# schemat.net
KiCad netlist of a schematic drawn in EAGLE
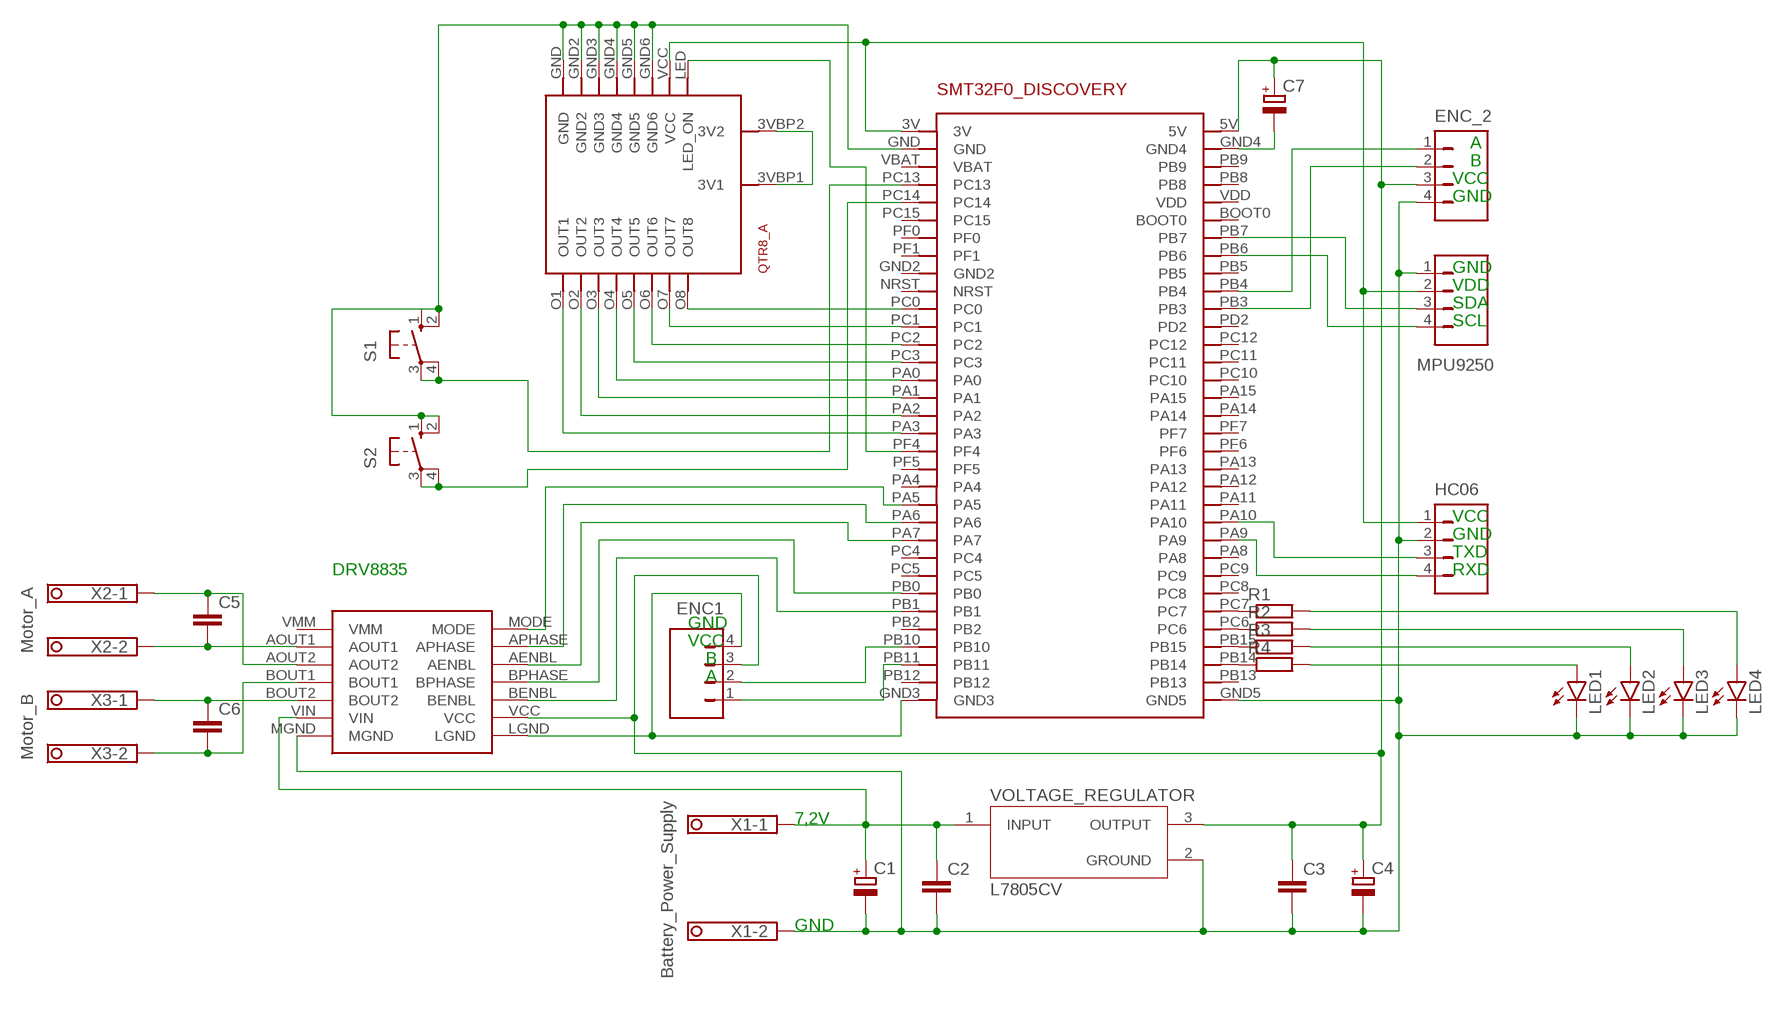
[diagram p0: schematic, sheet 1]

(export (version "E")
  (design (tool "Eeschema 10.0.6"))
  (components
    (comp (ref "C1")
      (value "CPOL-EUE2.5-6")
      (footprint "eagle-import:E2,5-6")
      (libsource (lib "eagle-import") (part "CPOL-EUE2.5-6"))
    )
    (comp (ref "C2")
      (value "C-EU025-024X044")
      (footprint "eagle-import:C025-024X044")
      (libsource (lib "eagle-import") (part "C-EU025-024X044"))
    )
    (comp (ref "C3")
      (value "C-EU025-024X044")
      (footprint "eagle-import:C025-024X044")
      (libsource (lib "eagle-import") (part "C-EU025-024X044"))
    )
    (comp (ref "C4")
      (value "CPOL-EUE2.5-6")
      (footprint "eagle-import:E2,5-6")
      (libsource (lib "eagle-import") (part "CPOL-EUE2.5-6"))
    )
    (comp (ref "C5")
      (value "C-EU025-024X044")
      (footprint "eagle-import:C025-024X044")
      (libsource (lib "eagle-import") (part "C-EU025-024X044"))
    )
    (comp (ref "C6")
      (value "C-EU025-024X044")
      (footprint "eagle-import:C025-024X044")
      (libsource (lib "eagle-import") (part "C-EU025-024X044"))
    )
    (comp (ref "C7")
      (value "CPOL-EUE2.5-6")
      (footprint "eagle-import:E2,5-6")
      (libsource (lib "eagle-import") (part "CPOL-EUE2.5-6"))
    )
    (comp (ref "DRV8835")
      (value "POLOLU_MOTOR_DRV8835THROUGHHOLE")
      (footprint "eagle-import:POLOLU_MOTOR_DRV_DRV8835")
      (libsource (lib "eagle-import") (part "POLOLU_MOTOR_DRV8835THROUGHHOLE"))
    )
    (comp (ref "ENC1")
      (value "JP4E")
      (footprint "eagle-import:JP4")
      (libsource (lib "eagle-import") (part "JP4E"))
    )
    (comp (ref "ENC_2")
      (value "JP4E")
      (footprint "eagle-import:JP4")
      (libsource (lib "eagle-import") (part "JP4E"))
    )
    (comp (ref "HC06")
      (value "JP4E")
      (footprint "eagle-import:JP4")
      (libsource (lib "eagle-import") (part "JP4E"))
    )
    (comp (ref "LED1")
      (value "LEDB152")
      (footprint "eagle-import:Q62902-B152")
      (libsource (lib "eagle-import") (part "LEDB152"))
    )
    (comp (ref "LED2")
      (value "LEDB152")
      (footprint "eagle-import:Q62902-B152")
      (libsource (lib "eagle-import") (part "LEDB152"))
    )
    (comp (ref "LED3")
      (value "LEDB152")
      (footprint "eagle-import:Q62902-B152")
      (libsource (lib "eagle-import") (part "LEDB152"))
    )
    (comp (ref "LED4")
      (value "LEDB152")
      (footprint "eagle-import:Q62902-B152")
      (libsource (lib "eagle-import") (part "LEDB152"))
    )
    (comp (ref "MPU9250")
      (value "JP4E")
      (footprint "eagle-import:JP4")
      (libsource (lib "eagle-import") (part "JP4E"))
    )
    (comp (ref "R1")
      (value "R-EU_0207/7")
      (footprint "eagle-import:0207_7")
      (libsource (lib "eagle-import") (part "R-EU_0207/7"))
    )
    (comp (ref "R2")
      (value "R-EU_0207/7")
      (footprint "eagle-import:0207_7")
      (libsource (lib "eagle-import") (part "R-EU_0207/7"))
    )
    (comp (ref "R3")
      (value "R-EU_0207/7")
      (footprint "eagle-import:0207_7")
      (libsource (lib "eagle-import") (part "R-EU_0207/7"))
    )
    (comp (ref "R4")
      (value "R-EU_0207/7")
      (footprint "eagle-import:0207_7")
      (libsource (lib "eagle-import") (part "R-EU_0207/7"))
    )
    (comp (ref "S1")
      (value "10-XX")
      (footprint "eagle-import:B3F-10XX")
      (fields (field (name "MPN") "B3F-1000"))
      (libsource (lib "eagle-import") (part "10-XX"))
    )
    (comp (ref "S2")
      (value "10-XX")
      (footprint "eagle-import:B3F-10XX")
      (fields (field (name "MPN") "B3F-1000"))
      (libsource (lib "eagle-import") (part "10-XX"))
    )
    (comp (ref "SMT32F0_DISCOVERY")
      (value "STM32F0_DISCOVERY")
      (footprint "eagle-import:STM32F0_DISCOVERY")
      (libsource (lib "eagle-import") (part "STM32F0_DISCOVERY"))
    )
    (comp (ref "U$1")
      (value "QTR8_A")
      (footprint "eagle-import:QTR8_A")
      (libsource (lib "eagle-import") (part "QTR8_A"))
    )
    (comp (ref "VOLTAGE_REGULATOR")
      (value "L7805CV")
      (footprint "eagle-import:TO255P1040X460X1968-3")
      (fields (field (name "MF") "STMicroelectronics"))
      (libsource (lib "eagle-import") (part "L7805CV"))
    )
    (comp (ref "X1")
      (value "Battery_Power_Supply")
      (footprint "eagle-import:1751248")
      (libsource (lib "eagle-import") (part "1751248"))
    )
    (comp (ref "X2")
      (value "Motor_A")
      (footprint "eagle-import:1751248")
      (libsource (lib "eagle-import") (part "1751248"))
    )
    (comp (ref "X3")
      (value "Motor_B")
      (footprint "eagle-import:1751248")
      (libsource (lib "eagle-import") (part "1751248"))
    )
  )
  (nets
    (net (code "1") (name "Net-(C7-Pad-)") (class "Default")
      (node (ref "C7") (pin "-") (pinfunction "-_-") (pintype "passive"))
      (node (ref "SMT32F0_DISCOVERY") (pin "GND4") (pinfunction "GND4_GND4") (pintype "bidirectional"))
    )
    (net (code "2") (name "Net-(DRV8835-PadAENBL)") (class "Default")
      (node (ref "DRV8835") (pin "AENBL") (pinfunction "AENBL_AENBL") (pintype "bidirectional"))
      (node (ref "SMT32F0_DISCOVERY") (pin "PA7") (pinfunction "PA7_PA7") (pintype "bidirectional"))
    )
    (net (code "3") (name "Net-(DRV8835-PadAPHASE)") (class "Default")
      (node (ref "DRV8835") (pin "APHASE") (pinfunction "APHASE_APHASE") (pintype "bidirectional"))
      (node (ref "SMT32F0_DISCOVERY") (pin "PA6") (pinfunction "PA6_PA6") (pintype "bidirectional"))
    )
    (net (code "4") (name "Net-(DRV8835-PadBENBL)") (class "Default")
      (node (ref "DRV8835") (pin "BENBL") (pinfunction "BENBL_BENBL") (pintype "bidirectional"))
      (node (ref "SMT32F0_DISCOVERY") (pin "PB1") (pinfunction "PB1_PB1") (pintype "bidirectional"))
    )
    (net (code "5") (name "Net-(DRV8835-PadBPHASE)") (class "Default")
      (node (ref "DRV8835") (pin "BPHASE") (pinfunction "BPHASE_BPHASE") (pintype "bidirectional"))
      (node (ref "SMT32F0_DISCOVERY") (pin "PB0") (pinfunction "PB0_PB0") (pintype "bidirectional"))
    )
    (net (code "6") (name "Net-(DRV8835-PadLGND)") (class "Default")
      (node (ref "DRV8835") (pin "LGND") (pinfunction "LGND_LGND") (pintype "bidirectional"))
      (node (ref "ENC1") (pin "4") (pinfunction "4_4") (pintype "passive"))
      (node (ref "SMT32F0_DISCOVERY") (pin "GND3") (pinfunction "GND3_GND3") (pintype "bidirectional"))
    )
    (net (code "7") (name "Net-(DRV8835-PadMODE)") (class "Default")
      (node (ref "DRV8835") (pin "MODE") (pinfunction "MODE_MODE") (pintype "bidirectional"))
      (node (ref "SMT32F0_DISCOVERY") (pin "PA5") (pinfunction "PA5_PA5") (pintype "bidirectional"))
    )
    (net (code "8") (name "Net-(ENC1-Pad1)") (class "Default")
      (node (ref "ENC1") (pin "1") (pinfunction "1_1") (pintype "passive"))
      (node (ref "SMT32F0_DISCOVERY") (pin "PB11") (pinfunction "PB11_PB11") (pintype "bidirectional"))
    )
    (net (code "9") (name "Net-(ENC1-Pad2)") (class "Default")
      (node (ref "ENC1") (pin "2") (pinfunction "2_2") (pintype "passive"))
      (node (ref "SMT32F0_DISCOVERY") (pin "PB10") (pinfunction "PB10_PB10") (pintype "bidirectional"))
    )
    (net (code "10") (name "Net-(ENC_2-Pad1)") (class "Default")
      (node (ref "ENC_2") (pin "1") (pinfunction "1_1") (pintype "passive"))
      (node (ref "SMT32F0_DISCOVERY") (pin "PB4") (pinfunction "PB4_PB4") (pintype "bidirectional"))
    )
    (net (code "11") (name "Net-(ENC_2-Pad2)") (class "Default")
      (node (ref "ENC_2") (pin "2") (pinfunction "2_2") (pintype "passive"))
      (node (ref "SMT32F0_DISCOVERY") (pin "PB3") (pinfunction "PB3_PB3") (pintype "bidirectional"))
    )
    (net (code "12") (name "Net-(HC06-Pad1)") (class "Default")
      (node (ref "HC06") (pin "1") (pinfunction "1_1") (pintype "passive"))
      (node (ref "MPU9250") (pin "2") (pinfunction "2_2") (pintype "passive"))
      (node (ref "SMT32F0_DISCOVERY") (pin "3V") (pinfunction "3V_3V") (pintype "bidirectional"))
      (node (ref "U$1") (pin "VCC") (pinfunction "VCC_VCC") (pintype "bidirectional"))
    )
    (net (code "13") (name "Net-(HC06-Pad3)") (class "Default")
      (node (ref "HC06") (pin "3") (pinfunction "3_3") (pintype "passive"))
      (node (ref "SMT32F0_DISCOVERY") (pin "PA10") (pinfunction "PA10_PA10") (pintype "bidirectional"))
    )
    (net (code "14") (name "Net-(HC06-Pad4)") (class "Default")
      (node (ref "HC06") (pin "4") (pinfunction "4_4") (pintype "passive"))
      (node (ref "SMT32F0_DISCOVERY") (pin "PA9") (pinfunction "PA9_PA9") (pintype "bidirectional"))
    )
    (net (code "15") (name "Net-(LED1-C)") (class "Default")
      (node (ref "C1") (pin "-") (pinfunction "-_-") (pintype "passive"))
      (node (ref "C2") (pin "2") (pinfunction "2_2") (pintype "passive"))
      (node (ref "C3") (pin "2") (pinfunction "2_2") (pintype "passive"))
      (node (ref "C4") (pin "-") (pinfunction "-_-") (pintype "passive"))
      (node (ref "DRV8835") (pin "MGND") (pinfunction "MGND_MGND") (pintype "bidirectional"))
      (node (ref "ENC_2") (pin "4") (pinfunction "4_4") (pintype "passive"))
      (node (ref "HC06") (pin "2") (pinfunction "2_2") (pintype "passive"))
      (node (ref "LED1") (pin "K") (pinfunction "C_K") (pintype "passive"))
      (node (ref "LED2") (pin "K") (pinfunction "C_K") (pintype "passive"))
      (node (ref "LED3") (pin "K") (pinfunction "C_K") (pintype "passive"))
      (node (ref "LED4") (pin "K") (pinfunction "C_K") (pintype "passive"))
      (node (ref "MPU9250") (pin "1") (pinfunction "1_1") (pintype "passive"))
      (node (ref "SMT32F0_DISCOVERY") (pin "GND5") (pinfunction "GND5_GND5") (pintype "bidirectional"))
      (node (ref "VOLTAGE_REGULATOR") (pin "2") (pinfunction "GROUND_2") (pintype "power_in"))
      (node (ref "X1") (pin "2") (pinfunction "K_2") (pintype "passive"))
    )
    (net (code "16") (name "Net-(LED1-PadA)") (class "Default")
      (node (ref "LED1") (pin "A") (pinfunction "A_A") (pintype "passive"))
      (node (ref "R4") (pin "2") (pinfunction "2_2") (pintype "passive"))
    )
    (net (code "17") (name "Net-(LED2-PadA)") (class "Default")
      (node (ref "LED2") (pin "A") (pinfunction "A_A") (pintype "passive"))
      (node (ref "R3") (pin "2") (pinfunction "2_2") (pintype "passive"))
    )
    (net (code "18") (name "Net-(LED3-PadA)") (class "Default")
      (node (ref "LED3") (pin "A") (pinfunction "A_A") (pintype "passive"))
      (node (ref "R2") (pin "2") (pinfunction "2_2") (pintype "passive"))
    )
    (net (code "19") (name "Net-(LED4-PadA)") (class "Default")
      (node (ref "LED4") (pin "A") (pinfunction "A_A") (pintype "passive"))
      (node (ref "R1") (pin "2") (pinfunction "2_2") (pintype "passive"))
    )
    (net (code "20") (name "Net-(MPU9250-Pad3)") (class "Default")
      (node (ref "MPU9250") (pin "3") (pinfunction "3_3") (pintype "passive"))
      (node (ref "SMT32F0_DISCOVERY") (pin "PB7") (pinfunction "PB7_PB7") (pintype "bidirectional"))
    )
    (net (code "21") (name "Net-(MPU9250-Pad4)") (class "Default")
      (node (ref "MPU9250") (pin "4") (pinfunction "4_4") (pintype "passive"))
      (node (ref "SMT32F0_DISCOVERY") (pin "PB6") (pinfunction "PB6_PB6") (pintype "bidirectional"))
    )
    (net (code "22") (name "Net-(R1-Pad1)") (class "Default")
      (node (ref "R1") (pin "1") (pinfunction "1_1") (pintype "passive"))
      (node (ref "SMT32F0_DISCOVERY") (pin "PC7") (pinfunction "PC7_PC7") (pintype "bidirectional"))
    )
    (net (code "23") (name "Net-(R2-Pad1)") (class "Default")
      (node (ref "R2") (pin "1") (pinfunction "1_1") (pintype "passive"))
      (node (ref "SMT32F0_DISCOVERY") (pin "PC6") (pinfunction "PC6_PC6") (pintype "bidirectional"))
    )
    (net (code "24") (name "Net-(R3-Pad1)") (class "Default")
      (node (ref "R3") (pin "1") (pinfunction "1_1") (pintype "passive"))
      (node (ref "SMT32F0_DISCOVERY") (pin "PB15") (pinfunction "PB15_PB15") (pintype "bidirectional"))
    )
    (net (code "25") (name "Net-(R4-Pad1)") (class "Default")
      (node (ref "R4") (pin "1") (pinfunction "1_1") (pintype "passive"))
      (node (ref "SMT32F0_DISCOVERY") (pin "PB14") (pinfunction "PB14_PB14") (pintype "bidirectional"))
    )
    (net (code "26") (name "Net-(S1-P)") (class "Default")
      (node (ref "S1") (pin "3") (pinfunction "P_3") (pintype "passive"))
      (node (ref "S1") (pin "4") (pinfunction "P1_4") (pintype "passive"))
      (node (ref "SMT32F0_DISCOVERY") (pin "PC13") (pinfunction "PC13_PC13") (pintype "bidirectional"))
    )
    (net (code "27") (name "Net-(S1-S)") (class "Default")
      (node (ref "S1") (pin "1") (pinfunction "S_1") (pintype "passive"))
      (node (ref "S1") (pin "2") (pinfunction "S1_2") (pintype "passive"))
      (node (ref "S2") (pin "1") (pinfunction "S_1") (pintype "passive"))
      (node (ref "S2") (pin "2") (pinfunction "S1_2") (pintype "passive"))
      (node (ref "SMT32F0_DISCOVERY") (pin "GND") (pinfunction "GND_GND") (pintype "bidirectional"))
      (node (ref "U$1") (pin "GND") (pinfunction "GND_GND") (pintype "bidirectional"))
      (node (ref "U$1") (pin "GND2") (pinfunction "GND2_GND2") (pintype "bidirectional"))
      (node (ref "U$1") (pin "GND3") (pinfunction "GND3_GND3") (pintype "bidirectional"))
      (node (ref "U$1") (pin "GND4") (pinfunction "GND4_GND4") (pintype "bidirectional"))
      (node (ref "U$1") (pin "GND5") (pinfunction "GND5_GND5") (pintype "bidirectional"))
      (node (ref "U$1") (pin "GND6") (pinfunction "GND6_GND6") (pintype "bidirectional"))
    )
    (net (code "28") (name "Net-(S2-P)") (class "Default")
      (node (ref "S2") (pin "3") (pinfunction "P_3") (pintype "passive"))
      (node (ref "S2") (pin "4") (pinfunction "P1_4") (pintype "passive"))
      (node (ref "SMT32F0_DISCOVERY") (pin "PC14") (pinfunction "PC14_PC14") (pintype "bidirectional"))
    )
    (net (code "29") (name "Net-(U$1-3V1)") (class "Default")
      (node (ref "U$1") (pin "3VBP1") (pinfunction "3V1_3VBP1") (pintype "bidirectional"))
      (node (ref "U$1") (pin "3VBP2") (pinfunction "3V2_3VBP2") (pintype "bidirectional"))
    )
    (net (code "30") (name "Net-(U$1-LED_ON)") (class "Default")
      (node (ref "SMT32F0_DISCOVERY") (pin "PF4") (pinfunction "PF4_PF4") (pintype "bidirectional"))
      (node (ref "U$1") (pin "LED") (pinfunction "LED_ON_LED") (pintype "bidirectional"))
    )
    (net (code "31") (name "Net-(U$1-OUT1)") (class "Default")
      (node (ref "SMT32F0_DISCOVERY") (pin "PA3") (pinfunction "PA3_PA3") (pintype "bidirectional"))
      (node (ref "U$1") (pin "O1") (pinfunction "OUT1_O1") (pintype "bidirectional"))
    )
    (net (code "32") (name "Net-(U$1-OUT2)") (class "Default")
      (node (ref "SMT32F0_DISCOVERY") (pin "PA2") (pinfunction "PA2_PA2") (pintype "bidirectional"))
      (node (ref "U$1") (pin "O2") (pinfunction "OUT2_O2") (pintype "bidirectional"))
    )
    (net (code "33") (name "Net-(U$1-OUT3)") (class "Default")
      (node (ref "SMT32F0_DISCOVERY") (pin "PA1") (pinfunction "PA1_PA1") (pintype "bidirectional"))
      (node (ref "U$1") (pin "O3") (pinfunction "OUT3_O3") (pintype "bidirectional"))
    )
    (net (code "34") (name "Net-(U$1-OUT4)") (class "Default")
      (node (ref "SMT32F0_DISCOVERY") (pin "PA0") (pinfunction "PA0_PA0") (pintype "bidirectional"))
      (node (ref "U$1") (pin "O4") (pinfunction "OUT4_O4") (pintype "bidirectional"))
    )
    (net (code "35") (name "Net-(U$1-OUT5)") (class "Default")
      (node (ref "SMT32F0_DISCOVERY") (pin "PC3") (pinfunction "PC3_PC3") (pintype "bidirectional"))
      (node (ref "U$1") (pin "O5") (pinfunction "OUT5_O5") (pintype "bidirectional"))
    )
    (net (code "36") (name "Net-(U$1-OUT6)") (class "Default")
      (node (ref "SMT32F0_DISCOVERY") (pin "PC2") (pinfunction "PC2_PC2") (pintype "bidirectional"))
      (node (ref "U$1") (pin "O6") (pinfunction "OUT6_O6") (pintype "bidirectional"))
    )
    (net (code "37") (name "Net-(U$1-OUT7)") (class "Default")
      (node (ref "SMT32F0_DISCOVERY") (pin "PC1") (pinfunction "PC1_PC1") (pintype "bidirectional"))
      (node (ref "U$1") (pin "O7") (pinfunction "OUT7_O7") (pintype "bidirectional"))
    )
    (net (code "38") (name "Net-(U$1-OUT8)") (class "Default")
      (node (ref "SMT32F0_DISCOVERY") (pin "PC0") (pinfunction "PC0_PC0") (pintype "bidirectional"))
      (node (ref "U$1") (pin "O8") (pinfunction "OUT8_O8") (pintype "bidirectional"))
    )
    (net (code "39") (name "Net-(VOLTAGE_REGULATOR-INPUT)") (class "Default")
      (node (ref "C1") (pin "+") (pinfunction "+_+") (pintype "passive"))
      (node (ref "C2") (pin "1") (pinfunction "1_1") (pintype "passive"))
      (node (ref "DRV8835") (pin "VIN") (pinfunction "VIN_VIN") (pintype "bidirectional"))
      (node (ref "VOLTAGE_REGULATOR") (pin "1") (pinfunction "INPUT_1") (pintype "input"))
      (node (ref "X1") (pin "1") (pinfunction "K_1") (pintype "passive"))
    )
    (net (code "40") (name "Net-(VOLTAGE_REGULATOR-OUTPUT)") (class "Default")
      (node (ref "C3") (pin "1") (pinfunction "1_1") (pintype "passive"))
      (node (ref "C4") (pin "+") (pinfunction "+_+") (pintype "passive"))
      (node (ref "C7") (pin "+") (pinfunction "+_+") (pintype "passive"))
      (node (ref "DRV8835") (pin "VCC") (pinfunction "VCC_VCC") (pintype "bidirectional"))
      (node (ref "ENC1") (pin "3") (pinfunction "3_3") (pintype "passive"))
      (node (ref "ENC_2") (pin "3") (pinfunction "3_3") (pintype "passive"))
      (node (ref "SMT32F0_DISCOVERY") (pin "5V") (pinfunction "5V_5V") (pintype "bidirectional"))
      (node (ref "VOLTAGE_REGULATOR") (pin "3") (pinfunction "OUTPUT_3") (pintype "output"))
    )
    (net (code "41") (name "Net-(X2A-K)") (class "Default")
      (node (ref "C5") (pin "1") (pinfunction "1_1") (pintype "passive"))
      (node (ref "DRV8835") (pin "AOUT2") (pinfunction "AOUT2_AOUT2") (pintype "bidirectional"))
      (node (ref "X2") (pin "1") (pinfunction "K_1") (pintype "passive"))
    )
    (net (code "42") (name "Net-(X2B-K)") (class "Default")
      (node (ref "C5") (pin "2") (pinfunction "2_2") (pintype "passive"))
      (node (ref "DRV8835") (pin "AOUT1") (pinfunction "AOUT1_AOUT1") (pintype "bidirectional"))
      (node (ref "X2") (pin "2") (pinfunction "K_2") (pintype "passive"))
    )
    (net (code "43") (name "Net-(X3A-K)") (class "Default")
      (node (ref "C6") (pin "1") (pinfunction "1_1") (pintype "passive"))
      (node (ref "DRV8835") (pin "BOUT2") (pinfunction "BOUT2_BOUT2") (pintype "bidirectional"))
      (node (ref "X3") (pin "1") (pinfunction "K_1") (pintype "passive"))
    )
    (net (code "44") (name "Net-(X3B-K)") (class "Default")
      (node (ref "C6") (pin "2") (pinfunction "2_2") (pintype "passive"))
      (node (ref "DRV8835") (pin "BOUT1") (pinfunction "BOUT1_BOUT1") (pintype "bidirectional"))
      (node (ref "X3") (pin "2") (pinfunction "K_2") (pintype "passive"))
    )
    (net (code "45") (name "unconnected-(DRV8835-PadVMM)") (class "Default")
      (node (ref "DRV8835") (pin "VMM") (pinfunction "VMM_VMM") (pintype "bidirectional"))
    )
    (net (code "46") (name "unconnected-(SMT32F0_DISCOVERY-PadBOOT0)") (class "Default")
      (node (ref "SMT32F0_DISCOVERY") (pin "BOOT0") (pinfunction "BOOT0_BOOT0") (pintype "bidirectional"))
    )
    (net (code "47") (name "unconnected-(SMT32F0_DISCOVERY-PadGND2)") (class "Default")
      (node (ref "SMT32F0_DISCOVERY") (pin "GND2") (pinfunction "GND2_GND2") (pintype "bidirectional"))
    )
    (net (code "48") (name "unconnected-(SMT32F0_DISCOVERY-PadNRST)") (class "Default")
      (node (ref "SMT32F0_DISCOVERY") (pin "NRST") (pinfunction "NRST_NRST") (pintype "bidirectional"))
    )
    (net (code "49") (name "unconnected-(SMT32F0_DISCOVERY-PadPA4)") (class "Default")
      (node (ref "SMT32F0_DISCOVERY") (pin "PA4") (pinfunction "PA4_PA4") (pintype "bidirectional"))
    )
    (net (code "50") (name "unconnected-(SMT32F0_DISCOVERY-PadPA8)") (class "Default")
      (node (ref "SMT32F0_DISCOVERY") (pin "PA8") (pinfunction "PA8_PA8") (pintype "bidirectional"))
    )
    (net (code "51") (name "unconnected-(SMT32F0_DISCOVERY-PadPA11)") (class "Default")
      (node (ref "SMT32F0_DISCOVERY") (pin "PA11") (pinfunction "PA11_PA11") (pintype "bidirectional"))
    )
    (net (code "52") (name "unconnected-(SMT32F0_DISCOVERY-PadPA12)") (class "Default")
      (node (ref "SMT32F0_DISCOVERY") (pin "PA12") (pinfunction "PA12_PA12") (pintype "bidirectional"))
    )
    (net (code "53") (name "unconnected-(SMT32F0_DISCOVERY-PadPA13)") (class "Default")
      (node (ref "SMT32F0_DISCOVERY") (pin "PA13") (pinfunction "PA13_PA13") (pintype "bidirectional"))
    )
    (net (code "54") (name "unconnected-(SMT32F0_DISCOVERY-PadPA14)") (class "Default")
      (node (ref "SMT32F0_DISCOVERY") (pin "PA14") (pinfunction "PA14_PA14") (pintype "bidirectional"))
    )
    (net (code "55") (name "unconnected-(SMT32F0_DISCOVERY-PadPA15)") (class "Default")
      (node (ref "SMT32F0_DISCOVERY") (pin "PA15") (pinfunction "PA15_PA15") (pintype "bidirectional"))
    )
    (net (code "56") (name "unconnected-(SMT32F0_DISCOVERY-PadPB2)") (class "Default")
      (node (ref "SMT32F0_DISCOVERY") (pin "PB2") (pinfunction "PB2_PB2") (pintype "bidirectional"))
    )
    (net (code "57") (name "unconnected-(SMT32F0_DISCOVERY-PadPB5)") (class "Default")
      (node (ref "SMT32F0_DISCOVERY") (pin "PB5") (pinfunction "PB5_PB5") (pintype "bidirectional"))
    )
    (net (code "58") (name "unconnected-(SMT32F0_DISCOVERY-PadPB8)") (class "Default")
      (node (ref "SMT32F0_DISCOVERY") (pin "PB8") (pinfunction "PB8_PB8") (pintype "bidirectional"))
    )
    (net (code "59") (name "unconnected-(SMT32F0_DISCOVERY-PadPB9)") (class "Default")
      (node (ref "SMT32F0_DISCOVERY") (pin "PB9") (pinfunction "PB9_PB9") (pintype "bidirectional"))
    )
    (net (code "60") (name "unconnected-(SMT32F0_DISCOVERY-PadPB12)") (class "Default")
      (node (ref "SMT32F0_DISCOVERY") (pin "PB12") (pinfunction "PB12_PB12") (pintype "bidirectional"))
    )
    (net (code "61") (name "unconnected-(SMT32F0_DISCOVERY-PadPB13)") (class "Default")
      (node (ref "SMT32F0_DISCOVERY") (pin "PB13") (pinfunction "PB13_PB13") (pintype "bidirectional"))
    )
    (net (code "62") (name "unconnected-(SMT32F0_DISCOVERY-PadPC4)") (class "Default")
      (node (ref "SMT32F0_DISCOVERY") (pin "PC4") (pinfunction "PC4_PC4") (pintype "bidirectional"))
    )
    (net (code "63") (name "unconnected-(SMT32F0_DISCOVERY-PadPC5)") (class "Default")
      (node (ref "SMT32F0_DISCOVERY") (pin "PC5") (pinfunction "PC5_PC5") (pintype "bidirectional"))
    )
    (net (code "64") (name "unconnected-(SMT32F0_DISCOVERY-PadPC8)") (class "Default")
      (node (ref "SMT32F0_DISCOVERY") (pin "PC8") (pinfunction "PC8_PC8") (pintype "bidirectional"))
    )
    (net (code "65") (name "unconnected-(SMT32F0_DISCOVERY-PadPC9)") (class "Default")
      (node (ref "SMT32F0_DISCOVERY") (pin "PC9") (pinfunction "PC9_PC9") (pintype "bidirectional"))
    )
    (net (code "66") (name "unconnected-(SMT32F0_DISCOVERY-PadPC10)") (class "Default")
      (node (ref "SMT32F0_DISCOVERY") (pin "PC10") (pinfunction "PC10_PC10") (pintype "bidirectional"))
    )
    (net (code "67") (name "unconnected-(SMT32F0_DISCOVERY-PadPC11)") (class "Default")
      (node (ref "SMT32F0_DISCOVERY") (pin "PC11") (pinfunction "PC11_PC11") (pintype "bidirectional"))
    )
    (net (code "68") (name "unconnected-(SMT32F0_DISCOVERY-PadPC12)") (class "Default")
      (node (ref "SMT32F0_DISCOVERY") (pin "PC12") (pinfunction "PC12_PC12") (pintype "bidirectional"))
    )
    (net (code "69") (name "unconnected-(SMT32F0_DISCOVERY-PadPC15)") (class "Default")
      (node (ref "SMT32F0_DISCOVERY") (pin "PC15") (pinfunction "PC15_PC15") (pintype "bidirectional"))
    )
    (net (code "70") (name "unconnected-(SMT32F0_DISCOVERY-PadPD2)") (class "Default")
      (node (ref "SMT32F0_DISCOVERY") (pin "PD2") (pinfunction "PD2_PD2") (pintype "bidirectional"))
    )
    (net (code "71") (name "unconnected-(SMT32F0_DISCOVERY-PadPF0)") (class "Default")
      (node (ref "SMT32F0_DISCOVERY") (pin "PF0") (pinfunction "PF0_PF0") (pintype "bidirectional"))
    )
    (net (code "72") (name "unconnected-(SMT32F0_DISCOVERY-PadPF1)") (class "Default")
      (node (ref "SMT32F0_DISCOVERY") (pin "PF1") (pinfunction "PF1_PF1") (pintype "bidirectional"))
    )
    (net (code "73") (name "unconnected-(SMT32F0_DISCOVERY-PadPF5)") (class "Default")
      (node (ref "SMT32F0_DISCOVERY") (pin "PF5") (pinfunction "PF5_PF5") (pintype "bidirectional"))
    )
    (net (code "74") (name "unconnected-(SMT32F0_DISCOVERY-PadPF6)") (class "Default")
      (node (ref "SMT32F0_DISCOVERY") (pin "PF6") (pinfunction "PF6_PF6") (pintype "bidirectional"))
    )
    (net (code "75") (name "unconnected-(SMT32F0_DISCOVERY-PadPF7)") (class "Default")
      (node (ref "SMT32F0_DISCOVERY") (pin "PF7") (pinfunction "PF7_PF7") (pintype "bidirectional"))
    )
    (net (code "76") (name "unconnected-(SMT32F0_DISCOVERY-PadVBAT)") (class "Default")
      (node (ref "SMT32F0_DISCOVERY") (pin "VBAT") (pinfunction "VBAT_VBAT") (pintype "bidirectional"))
    )
    (net (code "77") (name "unconnected-(SMT32F0_DISCOVERY-PadVDD)") (class "Default")
      (node (ref "SMT32F0_DISCOVERY") (pin "VDD") (pinfunction "VDD_VDD") (pintype "bidirectional"))
    )
  )
)
